# HeaderC.net
KiCad netlist of a schematic drawn in Altium Designer
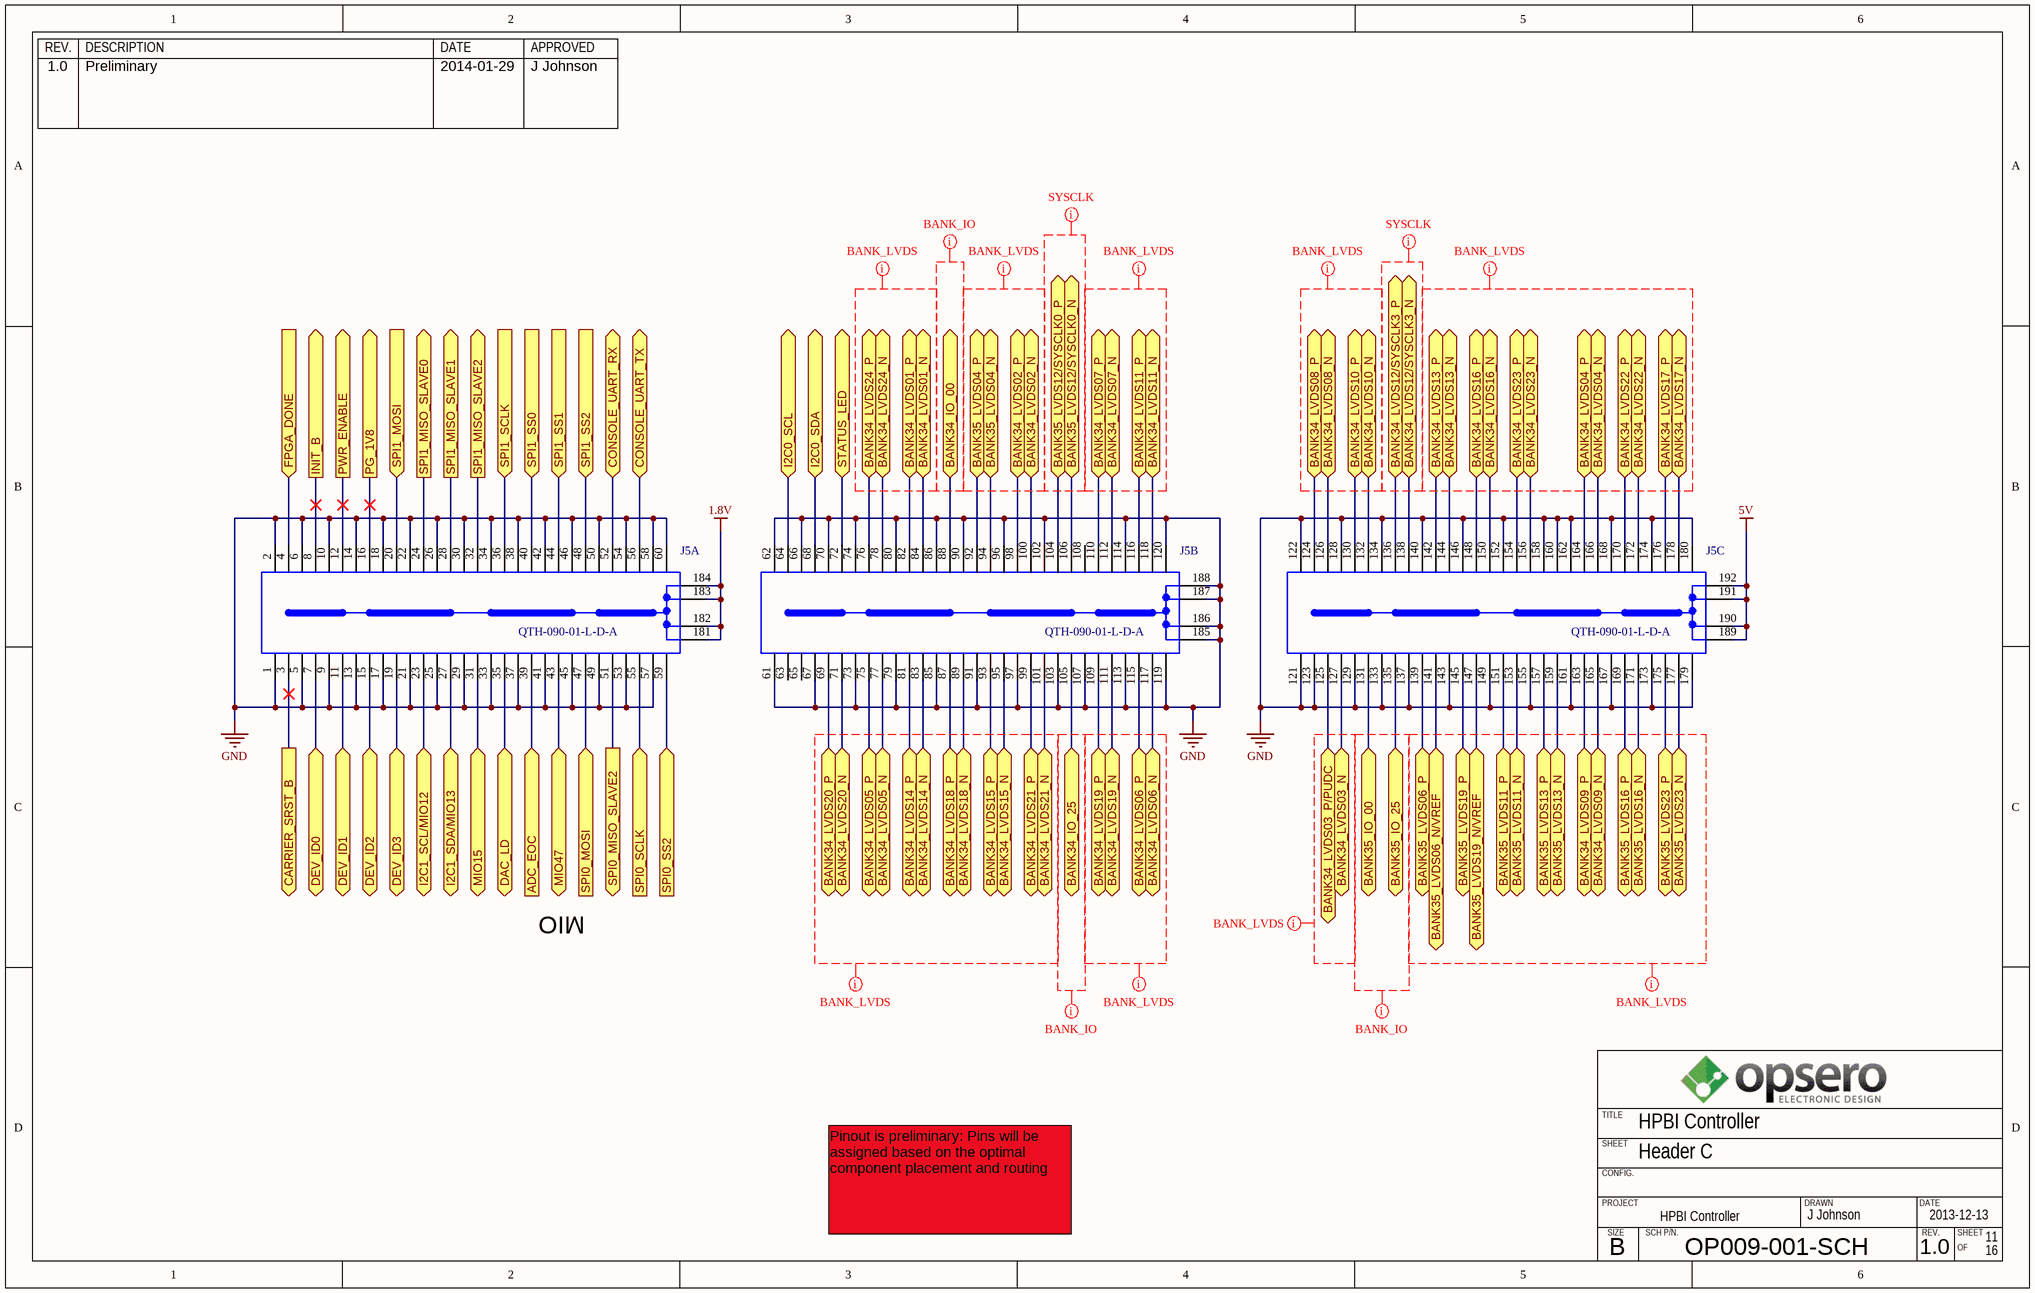
[diagram p0: HeaderC.SchDoc]

(export (version "E")
  (design (tool "Eeschema 10.0.6"))
  (components
    (comp (ref "J5")
      (value "QTH-090-01-L-D-A")
      (footprint "QTH-090-01-L-D-A")
      (description "Connector Header HS .5mm 180 pin DL AU")
      (libsource (lib "parts") (part "QTH-090-01-L-D-A"))
    )
  )
  (nets
    (net (code "1") (name "/ADC_EOC") (class "Default")
      (node (ref "J5") (pin "39") (pinfunction "39_39") (pintype "passive"))
    )
    (net (code "2") (name "/BANK34_IO_00") (class "Default")
      (node (ref "J5") (pin "88") (pinfunction "88_88") (pintype "passive"))
    )
    (net (code "3") (name "/BANK34_IO_25") (class "Default")
      (node (ref "J5") (pin "105") (pinfunction "105_105") (pintype "passive"))
    )
    (net (code "4") (name "/BANK34_LVDS01_N") (class "Default")
      (node (ref "J5") (pin "84") (pinfunction "84_84") (pintype "passive"))
    )
    (net (code "5") (name "/BANK34_LVDS01_P") (class "Default")
      (node (ref "J5") (pin "82") (pinfunction "82_82") (pintype "passive"))
    )
    (net (code "6") (name "/BANK34_LVDS02_N") (class "Default")
      (node (ref "J5") (pin "100") (pinfunction "100_100") (pintype "passive"))
    )
    (net (code "7") (name "/BANK34_LVDS02_P") (class "Default")
      (node (ref "J5") (pin "98") (pinfunction "98_98") (pintype "passive"))
    )
    (net (code "8") (name "/BANK34_LVDS03_N") (class "Default")
      (node (ref "J5") (pin "127") (pinfunction "127_127") (pintype "passive"))
    )
    (net (code "9") (name "/BANK34_LVDS03_P{slash}PUDC") (class "Default")
      (node (ref "J5") (pin "125") (pinfunction "125_125") (pintype "passive"))
    )
    (net (code "10") (name "/BANK34_LVDS04_N") (class "Default")
      (node (ref "J5") (pin "166") (pinfunction "166_166") (pintype "passive"))
    )
    (net (code "11") (name "/BANK34_LVDS04_P") (class "Default")
      (node (ref "J5") (pin "164") (pinfunction "164_164") (pintype "passive"))
    )
    (net (code "12") (name "/BANK34_LVDS05_N") (class "Default")
      (node (ref "J5") (pin "77") (pinfunction "77_77") (pintype "passive"))
    )
    (net (code "13") (name "/BANK34_LVDS05_P") (class "Default")
      (node (ref "J5") (pin "75") (pinfunction "75_75") (pintype "passive"))
    )
    (net (code "14") (name "/BANK34_LVDS06_N") (class "Default")
      (node (ref "J5") (pin "117") (pinfunction "117_117") (pintype "passive"))
    )
    (net (code "15") (name "/BANK34_LVDS06_P") (class "Default")
      (node (ref "J5") (pin "115") (pinfunction "115_115") (pintype "passive"))
    )
    (net (code "16") (name "/BANK34_LVDS07_N") (class "Default")
      (node (ref "J5") (pin "112") (pinfunction "112_112") (pintype "passive"))
    )
    (net (code "17") (name "/BANK34_LVDS07_P") (class "Default")
      (node (ref "J5") (pin "110") (pinfunction "110_110") (pintype "passive"))
    )
    (net (code "18") (name "/BANK34_LVDS08_N") (class "Default")
      (node (ref "J5") (pin "126") (pinfunction "126_126") (pintype "passive"))
    )
    (net (code "19") (name "/BANK34_LVDS08_P") (class "Default")
      (node (ref "J5") (pin "124") (pinfunction "124_124") (pintype "passive"))
    )
    (net (code "20") (name "/BANK34_LVDS09_N") (class "Default")
      (node (ref "J5") (pin "165") (pinfunction "165_165") (pintype "passive"))
    )
    (net (code "21") (name "/BANK34_LVDS09_P") (class "Default")
      (node (ref "J5") (pin "163") (pinfunction "163_163") (pintype "passive"))
    )
    (net (code "22") (name "/BANK34_LVDS10_N") (class "Default")
      (node (ref "J5") (pin "132") (pinfunction "132_132") (pintype "passive"))
    )
    (net (code "23") (name "/BANK34_LVDS10_P") (class "Default")
      (node (ref "J5") (pin "130") (pinfunction "130_130") (pintype "passive"))
    )
    (net (code "24") (name "/BANK34_LVDS11_N") (class "Default")
      (node (ref "J5") (pin "118") (pinfunction "118_118") (pintype "passive"))
    )
    (net (code "25") (name "/BANK34_LVDS11_P") (class "Default")
      (node (ref "J5") (pin "116") (pinfunction "116_116") (pintype "passive"))
    )
    (net (code "26") (name "/BANK34_LVDS12{slash}SYSCLK3_N") (class "Default")
      (node (ref "J5") (pin "138") (pinfunction "138_138") (pintype "passive"))
    )
    (net (code "27") (name "/BANK34_LVDS12{slash}SYSCLK3_P") (class "Default")
      (node (ref "J5") (pin "136") (pinfunction "136_136") (pintype "passive"))
    )
    (net (code "28") (name "/BANK34_LVDS13_N") (class "Default")
      (node (ref "J5") (pin "144") (pinfunction "144_144") (pintype "passive"))
    )
    (net (code "29") (name "/BANK34_LVDS13_P") (class "Default")
      (node (ref "J5") (pin "142") (pinfunction "142_142") (pintype "passive"))
    )
    (net (code "30") (name "/BANK34_LVDS14_N") (class "Default")
      (node (ref "J5") (pin "83") (pinfunction "83_83") (pintype "passive"))
    )
    (net (code "31") (name "/BANK34_LVDS14_P") (class "Default")
      (node (ref "J5") (pin "81") (pinfunction "81_81") (pintype "passive"))
    )
    (net (code "32") (name "/BANK34_LVDS15_N") (class "Default")
      (node (ref "J5") (pin "95") (pinfunction "95_95") (pintype "passive"))
    )
    (net (code "33") (name "/BANK34_LVDS15_P") (class "Default")
      (node (ref "J5") (pin "93") (pinfunction "93_93") (pintype "passive"))
    )
    (net (code "34") (name "/BANK34_LVDS16_N") (class "Default")
      (node (ref "J5") (pin "150") (pinfunction "150_150") (pintype "passive"))
    )
    (net (code "35") (name "/BANK34_LVDS16_P") (class "Default")
      (node (ref "J5") (pin "148") (pinfunction "148_148") (pintype "passive"))
    )
    (net (code "36") (name "/BANK34_LVDS17_N") (class "Default")
      (node (ref "J5") (pin "178") (pinfunction "178_178") (pintype "passive"))
    )
    (net (code "37") (name "/BANK34_LVDS17_P") (class "Default")
      (node (ref "J5") (pin "176") (pinfunction "176_176") (pintype "passive"))
    )
    (net (code "38") (name "/BANK34_LVDS18_N") (class "Default")
      (node (ref "J5") (pin "89") (pinfunction "89_89") (pintype "passive"))
    )
    (net (code "39") (name "/BANK34_LVDS18_P") (class "Default")
      (node (ref "J5") (pin "87") (pinfunction "87_87") (pintype "passive"))
    )
    (net (code "40") (name "/BANK34_LVDS19_N") (class "Default")
      (node (ref "J5") (pin "111") (pinfunction "111_111") (pintype "passive"))
    )
    (net (code "41") (name "/BANK34_LVDS19_P") (class "Default")
      (node (ref "J5") (pin "109") (pinfunction "109_109") (pintype "passive"))
    )
    (net (code "42") (name "/BANK34_LVDS20_N") (class "Default")
      (node (ref "J5") (pin "71") (pinfunction "71_71") (pintype "passive"))
    )
    (net (code "43") (name "/BANK34_LVDS20_P") (class "Default")
      (node (ref "J5") (pin "69") (pinfunction "69_69") (pintype "passive"))
    )
    (net (code "44") (name "/BANK34_LVDS21_N") (class "Default")
      (node (ref "J5") (pin "101") (pinfunction "101_101") (pintype "passive"))
    )
    (net (code "45") (name "/BANK34_LVDS21_P") (class "Default")
      (node (ref "J5") (pin "99") (pinfunction "99_99") (pintype "passive"))
    )
    (net (code "46") (name "/BANK34_LVDS22_N") (class "Default")
      (node (ref "J5") (pin "172") (pinfunction "172_172") (pintype "passive"))
    )
    (net (code "47") (name "/BANK34_LVDS22_P") (class "Default")
      (node (ref "J5") (pin "170") (pinfunction "170_170") (pintype "passive"))
    )
    (net (code "48") (name "/BANK34_LVDS23_N") (class "Default")
      (node (ref "J5") (pin "156") (pinfunction "156_156") (pintype "passive"))
    )
    (net (code "49") (name "/BANK34_LVDS23_P") (class "Default")
      (node (ref "J5") (pin "154") (pinfunction "154_154") (pintype "passive"))
    )
    (net (code "50") (name "/BANK34_LVDS24_N") (class "Default")
      (node (ref "J5") (pin "78") (pinfunction "78_78") (pintype "passive"))
    )
    (net (code "51") (name "/BANK34_LVDS24_P") (class "Default")
      (node (ref "J5") (pin "76") (pinfunction "76_76") (pintype "passive"))
    )
    (net (code "52") (name "/BANK35_IO_00") (class "Default")
      (node (ref "J5") (pin "131") (pinfunction "131_131") (pintype "passive"))
    )
    (net (code "53") (name "/BANK35_IO_25") (class "Default")
      (node (ref "J5") (pin "135") (pinfunction "135_135") (pintype "passive"))
    )
    (net (code "54") (name "/BANK35_LVDS04_N") (class "Default")
      (node (ref "J5") (pin "94") (pinfunction "94_94") (pintype "passive"))
    )
    (net (code "55") (name "/BANK35_LVDS04_P") (class "Default")
      (node (ref "J5") (pin "92") (pinfunction "92_92") (pintype "passive"))
    )
    (net (code "56") (name "/BANK35_LVDS06_N{slash}VREF") (class "Default")
      (node (ref "J5") (pin "141") (pinfunction "141_141") (pintype "passive"))
    )
    (net (code "57") (name "/BANK35_LVDS06_P") (class "Default")
      (node (ref "J5") (pin "139") (pinfunction "139_139") (pintype "passive"))
    )
    (net (code "58") (name "/BANK35_LVDS11_N") (class "Default")
      (node (ref "J5") (pin "153") (pinfunction "153_153") (pintype "passive"))
    )
    (net (code "59") (name "/BANK35_LVDS11_P") (class "Default")
      (node (ref "J5") (pin "151") (pinfunction "151_151") (pintype "passive"))
    )
    (net (code "60") (name "/BANK35_LVDS12{slash}SYSCLK0_N") (class "Default")
      (node (ref "J5") (pin "106") (pinfunction "106_106") (pintype "passive"))
    )
    (net (code "61") (name "/BANK35_LVDS12{slash}SYSCLK0_P") (class "Default")
      (node (ref "J5") (pin "104") (pinfunction "104_104") (pintype "passive"))
    )
    (net (code "62") (name "/BANK35_LVDS13_N") (class "Default")
      (node (ref "J5") (pin "159") (pinfunction "159_159") (pintype "passive"))
    )
    (net (code "63") (name "/BANK35_LVDS13_P") (class "Default")
      (node (ref "J5") (pin "157") (pinfunction "157_157") (pintype "passive"))
    )
    (net (code "64") (name "/BANK35_LVDS16_N") (class "Default")
      (node (ref "J5") (pin "171") (pinfunction "171_171") (pintype "passive"))
    )
    (net (code "65") (name "/BANK35_LVDS16_P") (class "Default")
      (node (ref "J5") (pin "169") (pinfunction "169_169") (pintype "passive"))
    )
    (net (code "66") (name "/BANK35_LVDS19_N{slash}VREF") (class "Default")
      (node (ref "J5") (pin "147") (pinfunction "147_147") (pintype "passive"))
    )
    (net (code "67") (name "/BANK35_LVDS19_P") (class "Default")
      (node (ref "J5") (pin "145") (pinfunction "145_145") (pintype "passive"))
    )
    (net (code "68") (name "/BANK35_LVDS23_N") (class "Default")
      (node (ref "J5") (pin "177") (pinfunction "177_177") (pintype "passive"))
    )
    (net (code "69") (name "/BANK35_LVDS23_P") (class "Default")
      (node (ref "J5") (pin "175") (pinfunction "175_175") (pintype "passive"))
    )
    (net (code "70") (name "/CARRIER_SRST_B") (class "Default")
      (node (ref "J5") (pin "3") (pinfunction "3_3") (pintype "passive"))
    )
    (net (code "71") (name "/CONSOLE_UART_RX") (class "Default")
      (node (ref "J5") (pin "52") (pinfunction "52_52") (pintype "passive"))
    )
    (net (code "72") (name "/CONSOLE_UART_TX") (class "Default")
      (node (ref "J5") (pin "56") (pinfunction "56_56") (pintype "passive"))
    )
    (net (code "73") (name "/DAC_LD") (class "Default")
      (node (ref "J5") (pin "35") (pinfunction "35_35") (pintype "passive"))
    )
    (net (code "74") (name "/DEV_ID0") (class "Default")
      (node (ref "J5") (pin "7") (pinfunction "7_7") (pintype "passive"))
    )
    (net (code "75") (name "/DEV_ID1") (class "Default")
      (node (ref "J5") (pin "11") (pinfunction "11_11") (pintype "passive"))
    )
    (net (code "76") (name "/DEV_ID2") (class "Default")
      (node (ref "J5") (pin "15") (pinfunction "15_15") (pintype "passive"))
    )
    (net (code "77") (name "/DEV_ID3") (class "Default")
      (node (ref "J5") (pin "19") (pinfunction "19_19") (pintype "passive"))
    )
    (net (code "78") (name "/FPGA_DONE") (class "Default")
      (node (ref "J5") (pin "4") (pinfunction "4_4") (pintype "passive"))
    )
    (net (code "79") (name "/I2C0_SCL") (class "Default")
      (node (ref "J5") (pin "64") (pinfunction "64_64") (pintype "passive"))
    )
    (net (code "80") (name "/I2C0_SDA") (class "Default")
      (node (ref "J5") (pin "68") (pinfunction "68_68") (pintype "passive"))
    )
    (net (code "81") (name "/I2C1_SCL{slash}MIO12") (class "Default")
      (node (ref "J5") (pin "23") (pinfunction "23_23") (pintype "passive"))
    )
    (net (code "82") (name "/I2C1_SDA{slash}MIO13") (class "Default")
      (node (ref "J5") (pin "27") (pinfunction "27_27") (pintype "passive"))
    )
    (net (code "83") (name "/INIT_B") (class "Default")
      (node (ref "J5") (pin "8") (pinfunction "8_8") (pintype "passive"))
    )
    (net (code "84") (name "/MIO15") (class "Default")
      (node (ref "J5") (pin "31") (pinfunction "31_31") (pintype "passive"))
    )
    (net (code "85") (name "/MIO47") (class "Default")
      (node (ref "J5") (pin "43") (pinfunction "43_43") (pintype "passive"))
    )
    (net (code "86") (name "/PG_1V8") (class "Default")
      (node (ref "J5") (pin "16") (pinfunction "16_16") (pintype "passive"))
    )
    (net (code "87") (name "/PWR_ENABLE") (class "Default")
      (node (ref "J5") (pin "12") (pinfunction "12_12") (pintype "passive"))
    )
    (net (code "88") (name "/SPI0_MISO_SLAVE2") (class "Default")
      (node (ref "J5") (pin "51") (pinfunction "51_51") (pintype "passive"))
    )
    (net (code "89") (name "/SPI0_MOSI") (class "Default")
      (node (ref "J5") (pin "47") (pinfunction "47_47") (pintype "passive"))
    )
    (net (code "90") (name "/SPI0_SCLK") (class "Default")
      (node (ref "J5") (pin "55") (pinfunction "55_55") (pintype "passive"))
    )
    (net (code "91") (name "/SPI0_SS2") (class "Default")
      (node (ref "J5") (pin "59") (pinfunction "59_59") (pintype "passive"))
    )
    (net (code "92") (name "/SPI1_MISO_SLAVE0") (class "Default")
      (node (ref "J5") (pin "24") (pinfunction "24_24") (pintype "passive"))
    )
    (net (code "93") (name "/SPI1_MISO_SLAVE1") (class "Default")
      (node (ref "J5") (pin "28") (pinfunction "28_28") (pintype "passive"))
    )
    (net (code "94") (name "/SPI1_MISO_SLAVE2") (class "Default")
      (node (ref "J5") (pin "32") (pinfunction "32_32") (pintype "passive"))
    )
    (net (code "95") (name "/SPI1_MOSI") (class "Default")
      (node (ref "J5") (pin "20") (pinfunction "20_20") (pintype "passive"))
    )
    (net (code "96") (name "/SPI1_SCLK") (class "Default")
      (node (ref "J5") (pin "36") (pinfunction "36_36") (pintype "passive"))
    )
    (net (code "97") (name "/SPI1_SS0") (class "Default")
      (node (ref "J5") (pin "40") (pinfunction "40_40") (pintype "passive"))
    )
    (net (code "98") (name "/SPI1_SS1") (class "Default")
      (node (ref "J5") (pin "44") (pinfunction "44_44") (pintype "passive"))
    )
    (net (code "99") (name "/SPI1_SS2") (class "Default")
      (node (ref "J5") (pin "48") (pinfunction "48_48") (pintype "passive"))
    )
    (net (code "100") (name "/STATUS_LED") (class "Default")
      (node (ref "J5") (pin "72") (pinfunction "72_72") (pintype "passive"))
    )
    (net (code "101") (name "1.8V") (class "Default")
      (node (ref "J5") (pin "181") (pinfunction "181_181") (pintype "passive"))
      (node (ref "J5") (pin "182") (pinfunction "182_182") (pintype "passive"))
      (node (ref "J5") (pin "183") (pinfunction "183_183") (pintype "passive"))
      (node (ref "J5") (pin "184") (pinfunction "184_184") (pintype "passive"))
    )
    (net (code "102") (name "5V") (class "Default")
      (node (ref "J5") (pin "189") (pinfunction "189_189") (pintype "passive"))
      (node (ref "J5") (pin "190") (pinfunction "190_190") (pintype "passive"))
      (node (ref "J5") (pin "191") (pinfunction "191_191") (pintype "passive"))
      (node (ref "J5") (pin "192") (pinfunction "192_192") (pintype "passive"))
    )
    (net (code "103") (name "GND") (class "Default")
      (node (ref "J5") (pin "1") (pinfunction "1_1") (pintype "passive"))
      (node (ref "J5") (pin "10") (pinfunction "10_10") (pintype "passive"))
      (node (ref "J5") (pin "102") (pinfunction "102_102") (pintype "passive"))
      (node (ref "J5") (pin "103") (pinfunction "103_103") (pintype "passive"))
      (node (ref "J5") (pin "107") (pinfunction "107_107") (pintype "passive"))
      (node (ref "J5") (pin "113") (pinfunction "113_113") (pintype "passive"))
      (node (ref "J5") (pin "114") (pinfunction "114_114") (pintype "passive"))
      (node (ref "J5") (pin "119") (pinfunction "119_119") (pintype "passive"))
      (node (ref "J5") (pin "120") (pinfunction "120_120") (pintype "passive"))
      (node (ref "J5") (pin "121") (pinfunction "121_121") (pintype "passive"))
      (node (ref "J5") (pin "122") (pinfunction "122_122") (pintype "passive"))
      (node (ref "J5") (pin "123") (pinfunction "123_123") (pintype "passive"))
      (node (ref "J5") (pin "128") (pinfunction "128_128") (pintype "passive"))
      (node (ref "J5") (pin "129") (pinfunction "129_129") (pintype "passive"))
      (node (ref "J5") (pin "13") (pinfunction "13_13") (pintype "passive"))
      (node (ref "J5") (pin "133") (pinfunction "133_133") (pintype "passive"))
      (node (ref "J5") (pin "134") (pinfunction "134_134") (pintype "passive"))
      (node (ref "J5") (pin "137") (pinfunction "137_137") (pintype "passive"))
      (node (ref "J5") (pin "14") (pinfunction "14_14") (pintype "passive"))
      (node (ref "J5") (pin "140") (pinfunction "140_140") (pintype "passive"))
      (node (ref "J5") (pin "143") (pinfunction "143_143") (pintype "passive"))
      (node (ref "J5") (pin "146") (pinfunction "146_146") (pintype "passive"))
      (node (ref "J5") (pin "149") (pinfunction "149_149") (pintype "passive"))
      (node (ref "J5") (pin "152") (pinfunction "152_152") (pintype "passive"))
      (node (ref "J5") (pin "155") (pinfunction "155_155") (pintype "passive"))
      (node (ref "J5") (pin "158") (pinfunction "158_158") (pintype "passive"))
      (node (ref "J5") (pin "160") (pinfunction "160_160") (pintype "passive"))
      (node (ref "J5") (pin "161") (pinfunction "161_161") (pintype "passive"))
      (node (ref "J5") (pin "162") (pinfunction "162_162") (pintype "passive"))
      (node (ref "J5") (pin "167") (pinfunction "167_167") (pintype "passive"))
      (node (ref "J5") (pin "168") (pinfunction "168_168") (pintype "passive"))
      (node (ref "J5") (pin "17") (pinfunction "17_17") (pintype "passive"))
      (node (ref "J5") (pin "173") (pinfunction "173_173") (pintype "passive"))
      (node (ref "J5") (pin "174") (pinfunction "174_174") (pintype "passive"))
      (node (ref "J5") (pin "179") (pinfunction "179_179") (pintype "passive"))
      (node (ref "J5") (pin "18") (pinfunction "18_18") (pintype "passive"))
      (node (ref "J5") (pin "180") (pinfunction "180_180") (pintype "passive"))
      (node (ref "J5") (pin "185") (pinfunction "185_185") (pintype "passive"))
      (node (ref "J5") (pin "186") (pinfunction "186_186") (pintype "passive"))
      (node (ref "J5") (pin "187") (pinfunction "187_187") (pintype "passive"))
      (node (ref "J5") (pin "188") (pinfunction "188_188") (pintype "passive"))
      (node (ref "J5") (pin "2") (pinfunction "2_2") (pintype "passive"))
      (node (ref "J5") (pin "21") (pinfunction "21_21") (pintype "passive"))
      (node (ref "J5") (pin "22") (pinfunction "22_22") (pintype "passive"))
      (node (ref "J5") (pin "25") (pinfunction "25_25") (pintype "passive"))
      (node (ref "J5") (pin "26") (pinfunction "26_26") (pintype "passive"))
      (node (ref "J5") (pin "29") (pinfunction "29_29") (pintype "passive"))
      (node (ref "J5") (pin "30") (pinfunction "30_30") (pintype "passive"))
      (node (ref "J5") (pin "33") (pinfunction "33_33") (pintype "passive"))
      (node (ref "J5") (pin "34") (pinfunction "34_34") (pintype "passive"))
      (node (ref "J5") (pin "37") (pinfunction "37_37") (pintype "passive"))
      (node (ref "J5") (pin "38") (pinfunction "38_38") (pintype "passive"))
      (node (ref "J5") (pin "41") (pinfunction "41_41") (pintype "passive"))
      (node (ref "J5") (pin "42") (pinfunction "42_42") (pintype "passive"))
      (node (ref "J5") (pin "45") (pinfunction "45_45") (pintype "passive"))
      (node (ref "J5") (pin "46") (pinfunction "46_46") (pintype "passive"))
      (node (ref "J5") (pin "49") (pinfunction "49_49") (pintype "passive"))
      (node (ref "J5") (pin "5") (pinfunction "5_5") (pintype "passive"))
      (node (ref "J5") (pin "50") (pinfunction "50_50") (pintype "passive"))
      (node (ref "J5") (pin "53") (pinfunction "53_53") (pintype "passive"))
      (node (ref "J5") (pin "54") (pinfunction "54_54") (pintype "passive"))
      (node (ref "J5") (pin "57") (pinfunction "57_57") (pintype "passive"))
      (node (ref "J5") (pin "58") (pinfunction "58_58") (pintype "passive"))
      (node (ref "J5") (pin "6") (pinfunction "6_6") (pintype "passive"))
      (node (ref "J5") (pin "60") (pinfunction "60_60") (pintype "passive"))
      (node (ref "J5") (pin "61") (pinfunction "61_61") (pintype "passive"))
      (node (ref "J5") (pin "62") (pinfunction "62_62") (pintype "passive"))
      (node (ref "J5") (pin "66") (pinfunction "66_66") (pintype "passive"))
      (node (ref "J5") (pin "67") (pinfunction "67_67") (pintype "passive"))
      (node (ref "J5") (pin "70") (pinfunction "70_70") (pintype "passive"))
      (node (ref "J5") (pin "73") (pinfunction "73_73") (pintype "passive"))
      (node (ref "J5") (pin "74") (pinfunction "74_74") (pintype "passive"))
      (node (ref "J5") (pin "79") (pinfunction "79_79") (pintype "passive"))
      (node (ref "J5") (pin "80") (pinfunction "80_80") (pintype "passive"))
      (node (ref "J5") (pin "85") (pinfunction "85_85") (pintype "passive"))
      (node (ref "J5") (pin "86") (pinfunction "86_86") (pintype "passive"))
      (node (ref "J5") (pin "9") (pinfunction "9_9") (pintype "passive"))
      (node (ref "J5") (pin "90") (pinfunction "90_90") (pintype "passive"))
      (node (ref "J5") (pin "91") (pinfunction "91_91") (pintype "passive"))
      (node (ref "J5") (pin "96") (pinfunction "96_96") (pintype "passive"))
      (node (ref "J5") (pin "97") (pinfunction "97_97") (pintype "passive"))
    )
    (net (code "104") (name "unconnected-(J5-Pad63)") (class "Default")
      (node (ref "J5") (pin "63") (pinfunction "63_63") (pintype "passive"))
    )
    (net (code "105") (name "unconnected-(J5-Pad65)") (class "Default")
      (node (ref "J5") (pin "65") (pinfunction "65_65") (pintype "passive"))
    )
    (net (code "106") (name "unconnected-(J5-Pad108)") (class "Default")
      (node (ref "J5") (pin "108") (pinfunction "108_108") (pintype "passive"))
    )
  )
)
